# NT_RadioModule.net
KiCad netlist of a schematic drawn in EAGLE
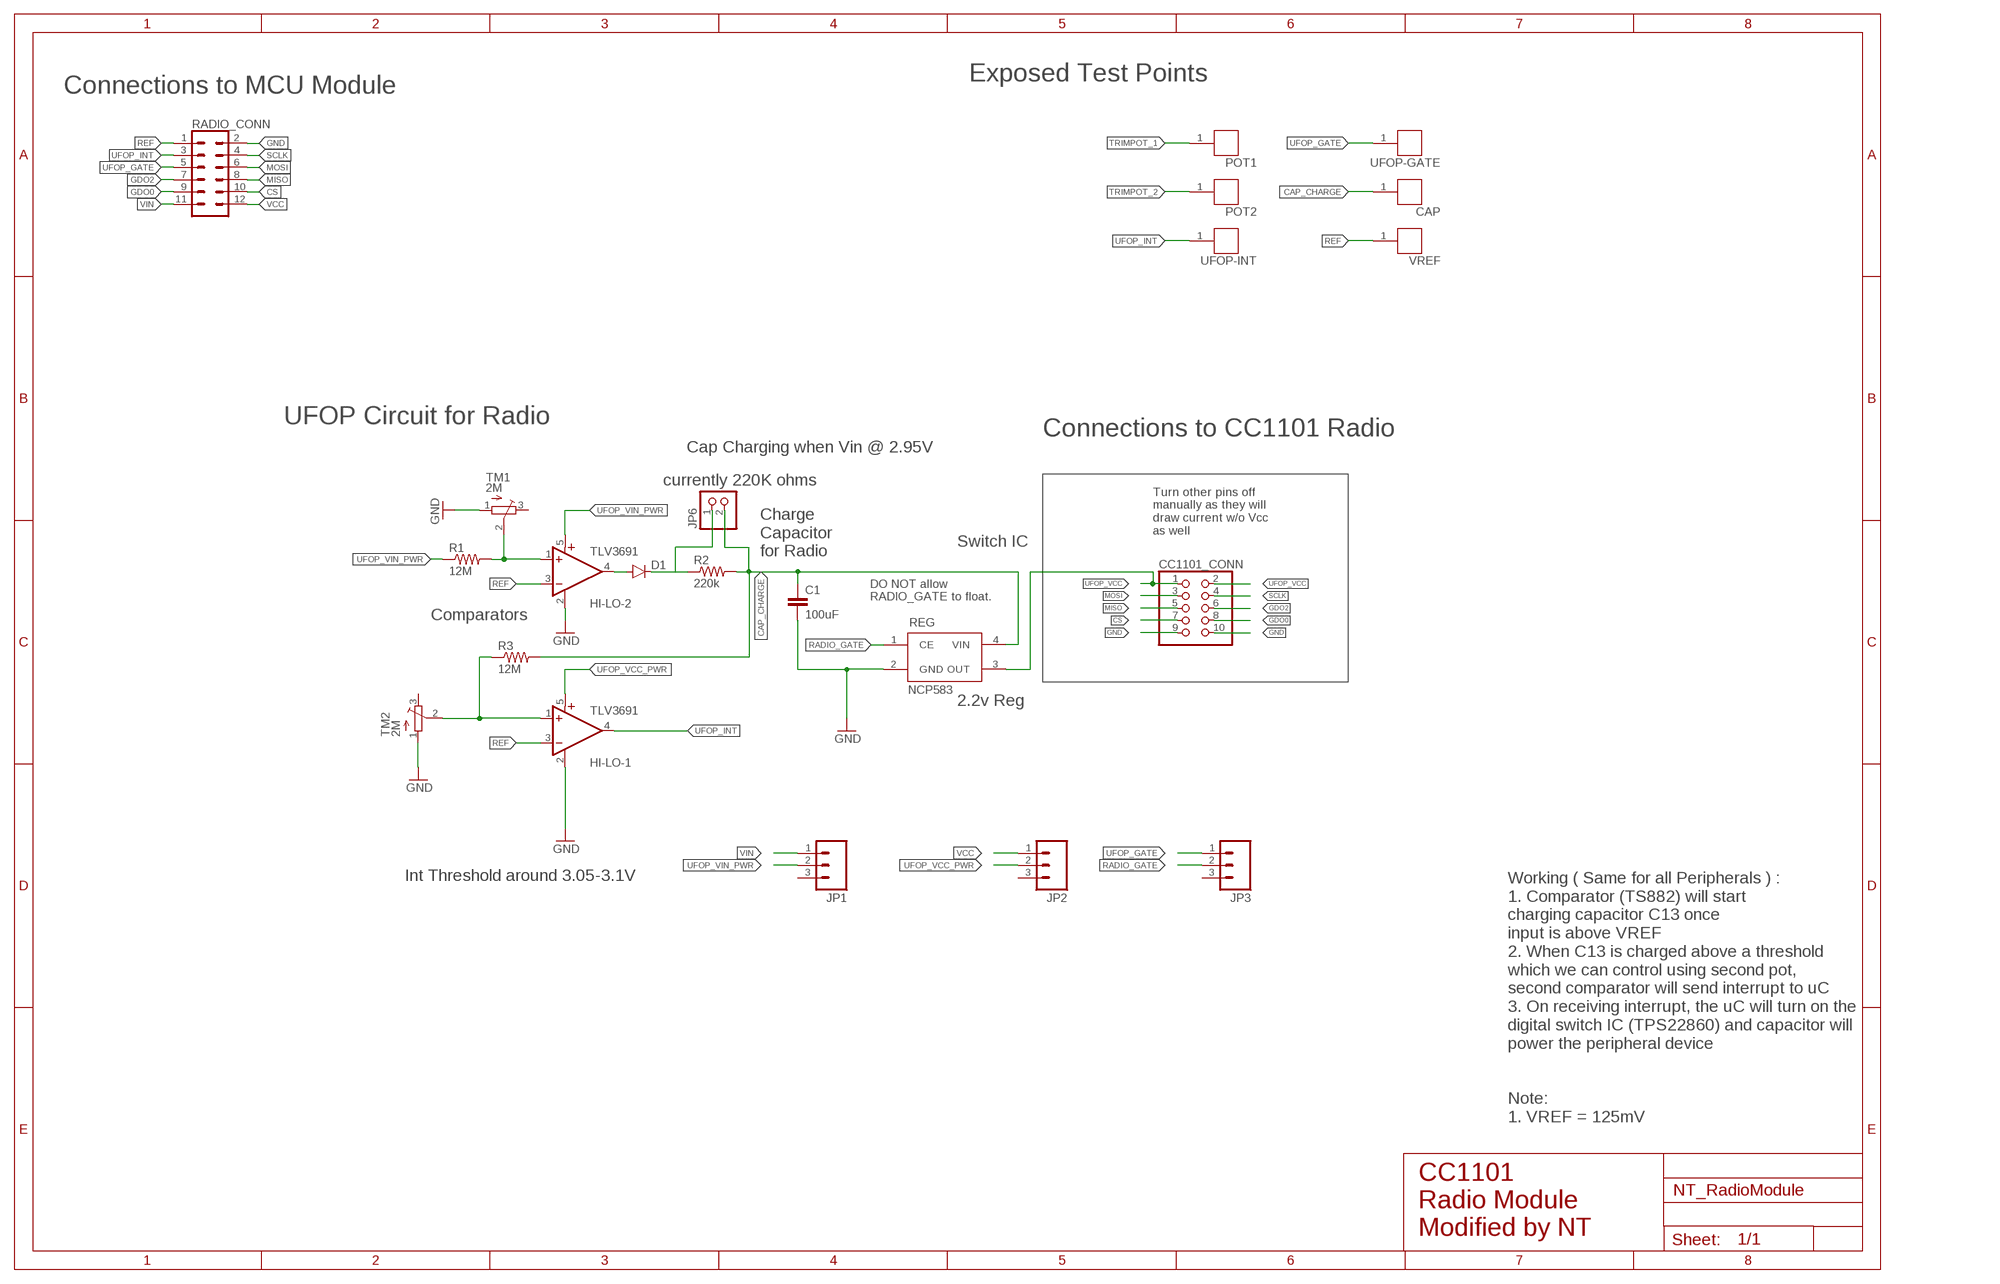
[diagram p0: schematic, sheet 1]

(export (version "E")
  (design (tool "Eeschema 10.0.6"))
  (components
    (comp (ref "C1")
      (value "100uF")
      (footprint "eagle-import:0603-CAP")
      (libsource (lib "eagle-import") (part "CAP0603-CAP"))
    )
    (comp (ref "CAP")
      (value "RCU-0C")
      (footprint "eagle-import:TE_RCU-0C")
      (fields
        (field (name "COMMENT") "RCU-0C _1625854-3_")
        (field (name "MF") "TE Connectivity")
        (field (name "TOLERANCE") "0%")
      )
      (libsource (lib "eagle-import") (part "RCU-0C"))
    )
    (comp (ref "CC1101_CONN")
      (value "PINHD-2X5")
      (footprint "eagle-import:2X05")
      (libsource (lib "eagle-import") (part "PINHD-2X5"))
    )
    (comp (ref "D1")
      (value "DIODESOD523")
      (footprint "eagle-import:SOD523")
      (libsource (lib "eagle-import") (part "DIODESOD523"))
    )
    (comp (ref "HI-LO-1")
      (value "TLV3691")
      (footprint "eagle-import:SC70-5")
      (libsource (lib "eagle-import") (part "TLV3691"))
    )
    (comp (ref "HI-LO-2")
      (value "TLV3691")
      (footprint "eagle-import:SC70-5")
      (libsource (lib "eagle-import") (part "TLV3691"))
    )
    (comp (ref "JP1")
      (value "M03")
      (footprint "eagle-import:1X03-1.27MM")
      (libsource (lib "eagle-import") (part "M03"))
    )
    (comp (ref "JP2")
      (value "M03")
      (footprint "eagle-import:1X03-1.27MM")
      (libsource (lib "eagle-import") (part "M03"))
    )
    (comp (ref "JP3")
      (value "M03")
      (footprint "eagle-import:1X03-1.27MM")
      (libsource (lib "eagle-import") (part "M03"))
    )
    (comp (ref "JP6")
      (value "PINHD-1X2")
      (footprint "eagle-import:1X02")
      (libsource (lib "eagle-import") (part "PINHD-1X2"))
    )
    (comp (ref "POT1")
      (value "RCU-0C")
      (footprint "eagle-import:TE_RCU-0C")
      (fields
        (field (name "COMMENT") "RCU-0C _1625854-3_")
        (field (name "MF") "TE Connectivity")
        (field (name "TOLERANCE") "0%")
      )
      (libsource (lib "eagle-import") (part "RCU-0C"))
    )
    (comp (ref "POT2")
      (value "RCU-0C")
      (footprint "eagle-import:TE_RCU-0C")
      (fields
        (field (name "COMMENT") "RCU-0C _1625854-3_")
        (field (name "MF") "TE Connectivity")
        (field (name "TOLERANCE") "0%")
      )
      (libsource (lib "eagle-import") (part "RCU-0C"))
    )
    (comp (ref "R1")
      (value "12M")
      (footprint "eagle-import:0603-RES")
      (libsource (lib "eagle-import") (part "RESISTOR0603"))
    )
    (comp (ref "R2")
      (value "220k")
      (footprint "eagle-import:0603-RES")
      (libsource (lib "eagle-import") (part "RESISTOR0603"))
    )
    (comp (ref "R3")
      (value "12M")
      (footprint "eagle-import:0603-RES")
      (libsource (lib "eagle-import") (part "RESISTOR0603"))
    )
    (comp (ref "RADIO_CONN")
      (value "CONN_06X2PTH_FEMALE")
      (footprint "eagle-import:2X6")
      (libsource (lib "eagle-import") (part "CONN_06X2PTH_FEMALE"))
    )
    (comp (ref "REG")
      (value "NCP583")
      (footprint "eagle-import:SC82-AB_1PRIMARY")
      (libsource (lib "eagle-import") (part "NCP583"))
    )
    (comp (ref "TM1")
      (value "2M")
      (footprint "eagle-import:TC33X")
      (libsource (lib "eagle-import") (part "TRIMPOTTC33X"))
    )
    (comp (ref "TM2")
      (value "2M")
      (footprint "eagle-import:TC33X")
      (libsource (lib "eagle-import") (part "TRIMPOTTC33X"))
    )
    (comp (ref "UFOP-GATE")
      (value "RCU-0C")
      (footprint "eagle-import:TE_RCU-0C")
      (fields
        (field (name "COMMENT") "RCU-0C _1625854-3_")
        (field (name "MF") "TE Connectivity")
        (field (name "TOLERANCE") "0%")
      )
      (libsource (lib "eagle-import") (part "RCU-0C"))
    )
    (comp (ref "UFOP-INT")
      (value "RCU-0C")
      (footprint "eagle-import:TE_RCU-0C")
      (fields
        (field (name "COMMENT") "RCU-0C _1625854-3_")
        (field (name "MF") "TE Connectivity")
        (field (name "TOLERANCE") "0%")
      )
      (libsource (lib "eagle-import") (part "RCU-0C"))
    )
    (comp (ref "VREF")
      (value "RCU-0C")
      (footprint "eagle-import:TE_RCU-0C")
      (fields
        (field (name "COMMENT") "RCU-0C _1625854-3_")
        (field (name "MF") "TE Connectivity")
        (field (name "TOLERANCE") "0%")
      )
      (libsource (lib "eagle-import") (part "RCU-0C"))
    )
  )
  (nets
    (net (code "1") (name "CAP_CHARGE") (class "Default")
      (node (ref "C1") (pin "1") (pinfunction "1_1") (pintype "passive"))
      (node (ref "CAP") (pin "1") (pinfunction "1_1") (pintype "passive"))
      (node (ref "JP6") (pin "2") (pinfunction "2_2") (pintype "passive"))
      (node (ref "R2") (pin "2") (pinfunction "2_2") (pintype "passive"))
      (node (ref "R3") (pin "2") (pinfunction "2_2") (pintype "passive"))
      (node (ref "REG") (pin "4") (pinfunction "VIN_4") (pintype "bidirectional"))
    )
    (net (code "2") (name "CS") (class "Default")
      (node (ref "CC1101_CONN") (pin "7") (pinfunction "7_7") (pintype "passive"))
      (node (ref "RADIO_CONN") (pin "10") (pinfunction "10_10") (pintype "passive"))
    )
    (net (code "3") (name "GDO0") (class "Default")
      (node (ref "CC1101_CONN") (pin "8") (pinfunction "8_8") (pintype "passive"))
      (node (ref "RADIO_CONN") (pin "9") (pinfunction "9_9") (pintype "passive"))
    )
    (net (code "4") (name "GDO2") (class "Default")
      (node (ref "CC1101_CONN") (pin "6") (pinfunction "6_6") (pintype "passive"))
      (node (ref "RADIO_CONN") (pin "7") (pinfunction "7_7") (pintype "passive"))
    )
    (net (code "5") (name "GND") (class "Default")
      (node (ref "C1") (pin "2") (pinfunction "2_2") (pintype "passive"))
      (node (ref "CC1101_CONN") (pin "10") (pinfunction "10_10") (pintype "passive"))
      (node (ref "CC1101_CONN") (pin "9") (pinfunction "9_9") (pintype "passive"))
      (node (ref "HI-LO-1") (pin "2") (pinfunction "GND_2") (pintype "power_in"))
      (node (ref "HI-LO-2") (pin "2") (pinfunction "GND_2") (pintype "power_in"))
      (node (ref "RADIO_CONN") (pin "2") (pinfunction "2_2") (pintype "passive"))
      (node (ref "REG") (pin "2") (pinfunction "GND_2") (pintype "bidirectional"))
      (node (ref "TM1") (pin "1") (pinfunction "A_1") (pintype "passive"))
      (node (ref "TM2") (pin "1") (pinfunction "A_1") (pintype "passive"))
    )
    (net (code "6") (name "MISO") (class "Default")
      (node (ref "CC1101_CONN") (pin "5") (pinfunction "5_5") (pintype "passive"))
      (node (ref "RADIO_CONN") (pin "8") (pinfunction "8_8") (pintype "passive"))
    )
    (net (code "7") (name "MOSI") (class "Default")
      (node (ref "CC1101_CONN") (pin "3") (pinfunction "3_3") (pintype "passive"))
      (node (ref "RADIO_CONN") (pin "6") (pinfunction "6_6") (pintype "passive"))
    )
    (net (code "8") (name "Net-(D1-PadC)") (class "Default")
      (node (ref "D1") (pin "C") (pinfunction "C_C") (pintype "passive"))
      (node (ref "JP6") (pin "1") (pinfunction "1_1") (pintype "passive"))
      (node (ref "R2") (pin "1") (pinfunction "1_1") (pintype "passive"))
    )
    (net (code "9") (name "Net-(HI-LO-2-OUT)") (class "Default")
      (node (ref "D1") (pin "A") (pinfunction "A_A") (pintype "passive"))
      (node (ref "HI-LO-2") (pin "4") (pinfunction "OUT_4") (pintype "output"))
    )
    (net (code "10") (name "RADIO_GATE") (class "Default")
      (node (ref "JP3") (pin "2") (pinfunction "2_2") (pintype "passive"))
      (node (ref "REG") (pin "1") (pinfunction "CE_1") (pintype "bidirectional"))
    )
    (net (code "11") (name "REF") (class "Default")
      (node (ref "HI-LO-1") (pin "3") (pinfunction "-IN_3") (pintype "input"))
      (node (ref "HI-LO-2") (pin "3") (pinfunction "-IN_3") (pintype "input"))
      (node (ref "RADIO_CONN") (pin "1") (pinfunction "1_1") (pintype "passive"))
      (node (ref "VREF") (pin "1") (pinfunction "1_1") (pintype "passive"))
    )
    (net (code "12") (name "SCLK") (class "Default")
      (node (ref "CC1101_CONN") (pin "4") (pinfunction "4_4") (pintype "passive"))
      (node (ref "RADIO_CONN") (pin "4") (pinfunction "4_4") (pintype "passive"))
    )
    (net (code "13") (name "TRIMPOT_1") (class "Default")
      (node (ref "HI-LO-2") (pin "1") (pinfunction "+IN_1") (pintype "input"))
      (node (ref "POT1") (pin "1") (pinfunction "1_1") (pintype "passive"))
      (node (ref "R1") (pin "2") (pinfunction "2_2") (pintype "passive"))
      (node (ref "TM1") (pin "2") (pinfunction "S_2") (pintype "passive"))
    )
    (net (code "14") (name "TRIMPOT_2") (class "Default")
      (node (ref "HI-LO-1") (pin "1") (pinfunction "+IN_1") (pintype "input"))
      (node (ref "POT2") (pin "1") (pinfunction "1_1") (pintype "passive"))
      (node (ref "R3") (pin "1") (pinfunction "1_1") (pintype "passive"))
      (node (ref "TM2") (pin "2") (pinfunction "S_2") (pintype "passive"))
    )
    (net (code "15") (name "UFOP_GATE") (class "Default")
      (node (ref "JP3") (pin "1") (pinfunction "1_1") (pintype "passive"))
      (node (ref "RADIO_CONN") (pin "5") (pinfunction "5_5") (pintype "passive"))
      (node (ref "UFOP-GATE") (pin "1") (pinfunction "1_1") (pintype "passive"))
    )
    (net (code "16") (name "UFOP_INT") (class "Default")
      (node (ref "HI-LO-1") (pin "4") (pinfunction "OUT_4") (pintype "output"))
      (node (ref "RADIO_CONN") (pin "3") (pinfunction "3_3") (pintype "passive"))
      (node (ref "UFOP-INT") (pin "1") (pinfunction "1_1") (pintype "passive"))
    )
    (net (code "17") (name "UFOP_VCC") (class "Default")
      (node (ref "CC1101_CONN") (pin "1") (pinfunction "1_1") (pintype "passive"))
      (node (ref "CC1101_CONN") (pin "2") (pinfunction "2_2") (pintype "passive"))
      (node (ref "REG") (pin "3") (pinfunction "OUT_3") (pintype "bidirectional"))
    )
    (net (code "18") (name "UFOP_VCC_PWR") (class "Default")
      (node (ref "HI-LO-1") (pin "5") (pinfunction "V+_5") (pintype "power_in"))
      (node (ref "JP2") (pin "2") (pinfunction "2_2") (pintype "passive"))
    )
    (net (code "19") (name "UFOP_VIN_PWR") (class "Default")
      (node (ref "HI-LO-2") (pin "5") (pinfunction "V+_5") (pintype "power_in"))
      (node (ref "JP1") (pin "2") (pinfunction "2_2") (pintype "passive"))
      (node (ref "R1") (pin "1") (pinfunction "1_1") (pintype "passive"))
    )
    (net (code "20") (name "VCC") (class "Default")
      (node (ref "JP2") (pin "1") (pinfunction "1_1") (pintype "passive"))
      (node (ref "RADIO_CONN") (pin "12") (pinfunction "12_12") (pintype "passive"))
    )
    (net (code "21") (name "VIN") (class "Default")
      (node (ref "JP1") (pin "1") (pinfunction "1_1") (pintype "passive"))
      (node (ref "RADIO_CONN") (pin "11") (pinfunction "11_11") (pintype "passive"))
    )
    (net (code "22") (name "unconnected-(JP1-Pad3)") (class "Default")
      (node (ref "JP1") (pin "3") (pinfunction "3_3") (pintype "passive"))
    )
    (net (code "23") (name "unconnected-(JP2-Pad3)") (class "Default")
      (node (ref "JP2") (pin "3") (pinfunction "3_3") (pintype "passive"))
    )
    (net (code "24") (name "unconnected-(JP3-Pad3)") (class "Default")
      (node (ref "JP3") (pin "3") (pinfunction "3_3") (pintype "passive"))
    )
    (net (code "25") (name "unconnected-(TM1-E-Pad3)") (class "Default")
      (node (ref "TM1") (pin "3") (pinfunction "E_3") (pintype "passive"))
    )
    (net (code "26") (name "unconnected-(TM2-E-Pad3)") (class "Default")
      (node (ref "TM2") (pin "3") (pinfunction "E_3") (pintype "passive"))
    )
  )
)
